# CYAN_EVSE_Power_board_v1_0.net
KiCad netlist of a schematic drawn in Altium Designer
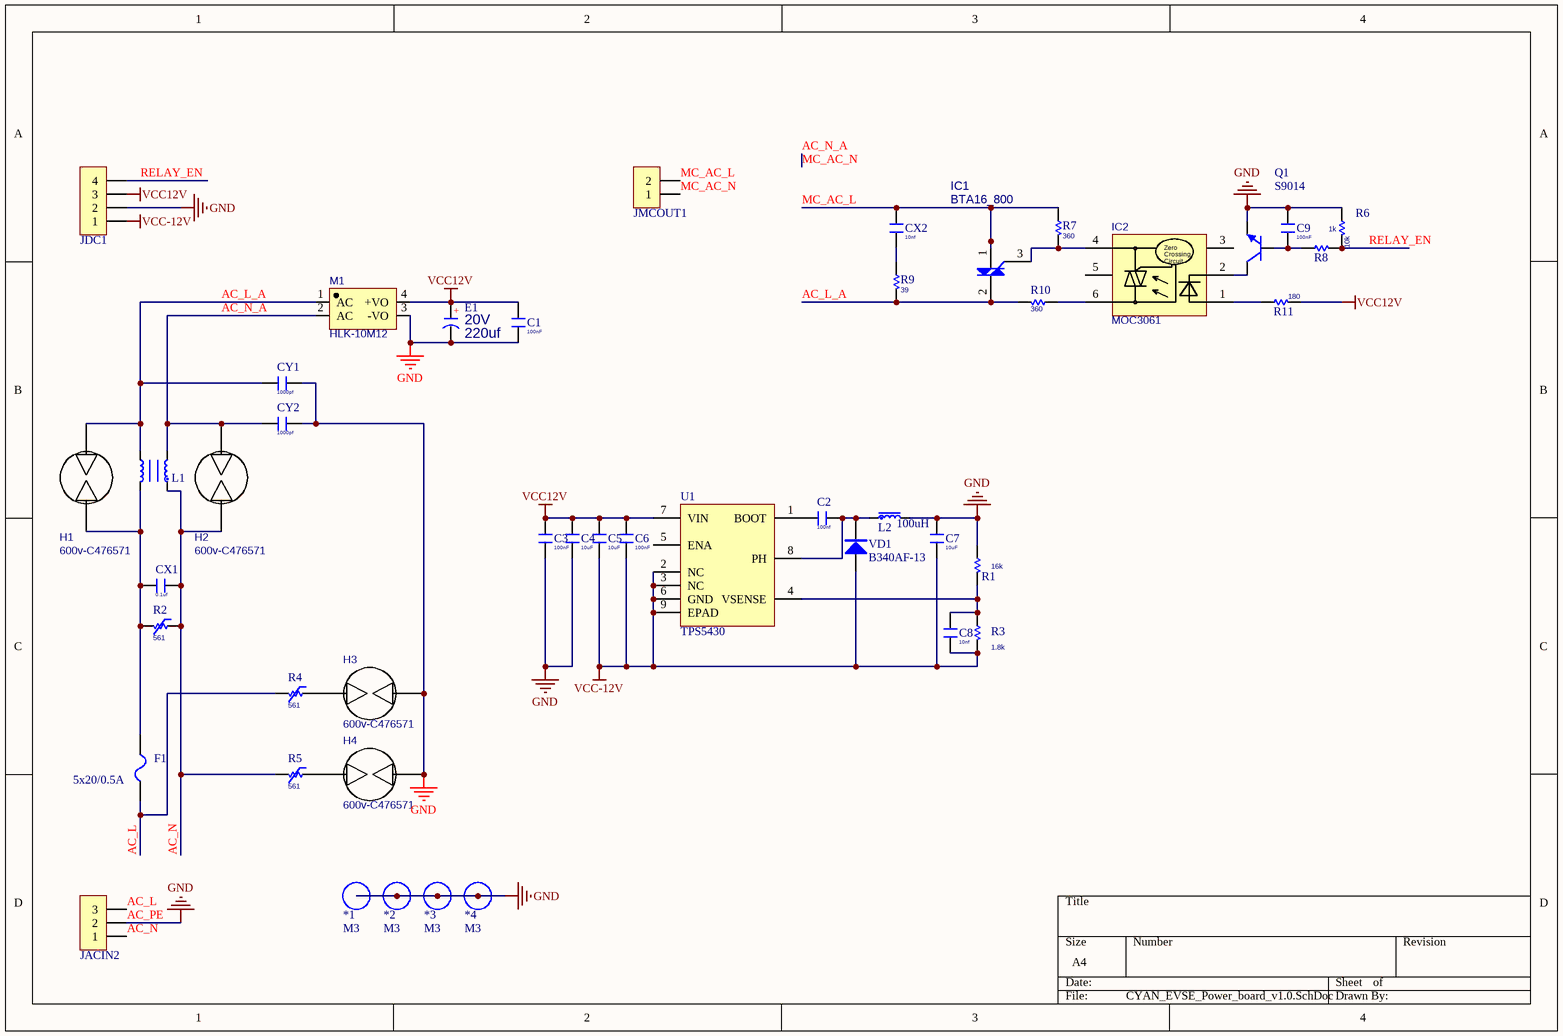
[diagram p0: CYAN_EVSE_Power_board_v1.0.SchDoc]

(export (version "E")
  (design (tool "Eeschema 10.0.6"))
  (components
    (comp (ref "*1")
      (value "M3")
      (footprint "M3 125X300")
      (description "铜柱孔")
      (libsource (lib "未分类器件") (part "M3"))
    )
    (comp (ref "*2")
      (value "M3")
      (footprint "M3 125X300")
      (description "铜柱孔")
      (libsource (lib "未分类器件") (part "M3"))
    )
    (comp (ref "*3")
      (value "M3")
      (footprint "M3 125X300")
      (description "铜柱孔")
      (libsource (lib "未分类器件") (part "M3"))
    )
    (comp (ref "*4")
      (value "M3")
      (footprint "M3 125X300")
      (description "铜柱孔")
      (libsource (lib "未分类器件") (part "M3"))
    )
    (comp (ref "C1")
      (value "100nF")
      (footprint "C 0805")
      (description "无极性贴片电容")
      (fields (field (name "VOLTAGE") "25V") (field (name "Comment") "C"))
      (libsource (lib "电阻-电容-电感") (part "C"))
    )
    (comp (ref "C2")
      (value "100nf")
      (footprint "C 0805")
      (description "无极性贴片电容")
      (fields (field (name "VOLTAGE") "50V") (field (name "Comment") "C"))
      (libsource (lib "电阻-电容-电感") (part "C"))
    )
    (comp (ref "C3")
      (value "100nF")
      (footprint "C 0805")
      (description "无极性贴片电容")
      (fields (field (name "VOLTAGE") "50V") (field (name "Comment") "C"))
      (libsource (lib "电阻-电容-电感") (part "C"))
    )
    (comp (ref "C4")
      (value "10uF")
      (footprint "C 0805")
      (description "无极性贴片电容")
      (fields (field (name "VOLTAGE") "50V") (field (name "Comment") "C"))
      (libsource (lib "电阻-电容-电感") (part "C"))
    )
    (comp (ref "C5")
      (value "10uF")
      (footprint "C 0805")
      (description "无极性贴片电容")
      (fields (field (name "VOLTAGE") "50V") (field (name "Comment") "C"))
      (libsource (lib "电阻-电容-电感") (part "C"))
    )
    (comp (ref "C6")
      (value "100nF")
      (footprint "C 0805")
      (description "无极性贴片电容")
      (fields (field (name "VOLTAGE") "50V") (field (name "Comment") "C"))
      (libsource (lib "电阻-电容-电感") (part "C"))
    )
    (comp (ref "C7")
      (value "10uF")
      (footprint "C 0805")
      (description "无极性贴片电容")
      (fields (field (name "VOLTAGE") "25V") (field (name "Comment") "C"))
      (libsource (lib "电阻-电容-电感") (part "C"))
    )
    (comp (ref "C8")
      (value "10nf")
      (footprint "C 0805")
      (description "无极性贴片电容")
      (fields (field (name "VOLTAGE") "50V") (field (name "Comment") "C"))
      (libsource (lib "电阻-电容-电感") (part "C"))
    )
    (comp (ref "C9")
      (value "100nF")
      (footprint "C 0805")
      (description "无极性贴片电容")
      (fields (field (name "VOLTAGE") "20V") (field (name "Comment") "C"))
      (libsource (lib "电阻-电容-电感") (part "C"))
    )
    (comp (ref "CX1")
      (value "0.1uf")
      (footprint "CX 10*13*11")
      (description "X电容")
      (fields (field (name "VOLTAGE") "10v") (field (name "Comment") "MKP-0.1uF275V"))
      (libsource (lib "电阻-电容-电感") (part "C-CX"))
    )
    (comp (ref "CX2")
      (value "10nf")
      (footprint "CX 10*13*11")
      (description "X电容")
      (fields (field (name "VOLTAGE") "440V") (field (name "Comment") "X1 安规电容"))
      (libsource (lib "电阻-电容-电感") (part "C-CX"))
    )
    (comp (ref "CY1")
      (value "1000pf")
      (footprint "CY 7.5*8*4")
      (description "高压陶瓷电容，Y电容")
      (fields (field (name "VOLTAGE") "250v") (field (name "Comment") "DCF102M26Y5VQ6B"))
      (libsource (lib "电阻-电容-电感") (part "C-CY"))
    )
    (comp (ref "CY2")
      (value "1000pf")
      (footprint "CY 7.5*8*4")
      (description "高压陶瓷电容，Y电容")
      (fields (field (name "VOLTAGE") "250v") (field (name "Comment") "DCF102M26Y5VQ6B"))
      (libsource (lib "电阻-电容-电感") (part "C-CY"))
    )
    (comp (ref "E1")
      (value "220uf")
      (footprint "CM D(6.3*5.4)")
      (description "贴片电解电容")
      (fields (field (name "VOLTAGE") "20V") (field (name "Comment") "C-CM"))
      (libsource (lib "电阻-电容-电感") (part "C-CM"))
    )
    (comp (ref "F1")
      (value "5x20/0.5A")
      (footprint "FU BLX-A")
      (description "5*20保险丝")
      (libsource (lib "保险丝-晶振") (part "FU 5x20"))
    )
    (comp (ref "H1")
      (value "600v-C476571")
      (footprint "GDT_SMD_L4.5-W3.2")
      (description "气体放电管")
      (libsource (lib "保险丝-晶振") (part "GDT"))
    )
    (comp (ref "H2")
      (value "600v-C476571")
      (footprint "GDT_SMD_L4.5-W3.2")
      (description "气体放电管")
      (libsource (lib "保险丝-晶振") (part "GDT"))
    )
    (comp (ref "H3")
      (value "600v-C476571")
      (footprint "GDT_SMD_L4.5-W3.2")
      (description "气体放电管")
      (libsource (lib "保险丝-晶振") (part "GDT"))
    )
    (comp (ref "H4")
      (value "600v-C476571")
      (footprint "GDT_SMD_L4.5-W3.2")
      (description "气体放电管")
      (libsource (lib "保险丝-晶振") (part "GDT"))
    )
    (comp (ref "IC1")
      (value "BTA16_800")
      (footprint "to:TO220A")
      (description "双向可控硅")
      (libsource (lib "场效应管-可控硅") (part "BTA12_600"))
    )
    (comp (ref "IC2")
      (value "MOC3061")
      (footprint "DIP6-300")
      (description "4(6)00v 带过0检测 光电可控硅 led电流15ma 1.3v")
      (fields (field (name "BOM_MANUFACTURER PART") "MOC3041M") (field (name "BOM_SUPPLIER PART") "C8921"))
      (libsource (lib "IC芯片") (part "MOC304(6)1"))
    )
    (comp (ref "JACIN2")
      (value "HDR-1X3")
      (footprint "KF2EDGK5.0-3P_H")
      (description "3P接插件")
      (libsource (lib "接插件") (part "Header 3"))
    )
    (comp (ref "JDC1")
      (value "HDR-1X4")
      (footprint "MC 1,5/ 4-G-3,81")
      (description "4P接插件")
      (libsource (lib "接插件") (part "Header 4"))
    )
    (comp (ref "JMCOUT1")
      (value "HDR-1X2")
      (footprint "MC 1,5/ 2-G-3,81")
      (description "2P接插件")
      (libsource (lib "接插件") (part "Header 2"))
    )
    (comp (ref "L1")
      (value "15mH")
      (footprint "UU9.8")
      (description "共模电感")
      (libsource (lib "电阻-电容-电感") (part "L-CMC"))
    )
    (comp (ref "L2")
      (value "100uH")
      (footprint "CD75")
      (description "贴片功率电感")
      (libsource (lib "电阻-电容-电感") (part "L-CD"))
    )
    (comp (ref "M1")
      (value "HLK-10M12")
      (footprint "PWRM-TH_HLK-10MXX")
      (description "HILINK 10W AC-DC 模块")
      (libsource (lib "模块") (part "HLK-10MXX"))
    )
    (comp (ref "Q1")
      (value "S9014")
      (footprint "SOT23-3N")
      (description "低噪放大-NPN型")
      (libsource (lib "三极管") (part "9014-SMD"))
    )
    (comp (ref "R1")
      (value "16k")
      (footprint "R 0805")
      (description "贴片电阻")
      (fields (field (name "Comment") "R"))
      (libsource (lib "电阻-电容-电感") (part "R"))
    )
    (comp (ref "R2")
      (value "561")
      (footprint "VDR 10D-7.5")
      (description "压敏电阻")
      (fields (field (name "Comment") "10d561k"))
      (libsource (lib "电阻-电容-电感") (part "R_VDR"))
    )
    (comp (ref "R3")
      (value "1.8k")
      (footprint "R 0805")
      (description "贴片电阻")
      (fields (field (name "Comment") "R"))
      (libsource (lib "电阻-电容-电感") (part "R"))
    )
    (comp (ref "R4")
      (value "561")
      (footprint "VDR 10D-7.5")
      (description "压敏电阻")
      (fields (field (name "Comment") "10d561k"))
      (libsource (lib "电阻-电容-电感") (part "R_VDR"))
    )
    (comp (ref "R5")
      (value "561")
      (footprint "VDR 10D-7.5")
      (description "压敏电阻")
      (fields (field (name "Comment") "10d561k"))
      (libsource (lib "电阻-电容-电感") (part "R_VDR"))
    )
    (comp (ref "R6")
      (value "10k")
      (footprint "R 0805")
      (description "贴片电阻")
      (fields (field (name "Comment") "R"))
      (libsource (lib "电阻-电容-电感") (part "R"))
    )
    (comp (ref "R7")
      (value "360")
      (footprint "RS 1/2W")
      (description "直插色环电阻")
      (fields (field (name "Comment") "R-CRR"))
      (libsource (lib "电阻-电容-电感") (part "R-CRR"))
    )
    (comp (ref "R8")
      (value "1k")
      (footprint "R 0805")
      (description "贴片电阻")
      (fields (field (name "Comment") "R"))
      (libsource (lib "电阻-电容-电感") (part "R"))
    )
    (comp (ref "R9")
      (value "39")
      (footprint "RS 2W")
      (description "直插色环电阻")
      (fields (field (name "Comment") "R-CRR"))
      (libsource (lib "电阻-电容-电感") (part "R-CRR"))
    )
    (comp (ref "R10")
      (value "360")
      (footprint "RS 1/2W")
      (description "直插色环电阻")
      (fields (field (name "Comment") "R-CRR"))
      (libsource (lib "电阻-电容-电感") (part "R-CRR"))
    )
    (comp (ref "R11")
      (value "180")
      (footprint "R 0805")
      (description "贴片电阻")
      (fields (field (name "Comment") "R"))
      (libsource (lib "电阻-电容-电感") (part "R"))
    )
    (comp (ref "U1")
      (value "TPS5430")
      (footprint "SOP8_EPAD_VIA")
      (description "3A 36v buck控制器，内置fet")
      (libsource (lib "IC芯片") (part "TPS5430"))
    )
    (comp (ref "VD1")
      (value "B340AF-13")
      (footprint "SMA")
      (description "肖特基二极管")
      (libsource (lib "二极管-整流桥") (part "SS14"))
    )
  )
  (nets
    (net (code "1") (name "/AC_L") (class "Default")
      (node (ref "F1") (pin "2") (pinfunction "2_2") (pintype "passive"))
      (node (ref "JACIN2") (pin "3") (pinfunction "3_3") (pintype "passive"))
      (node (ref "R4") (pin "2") (pinfunction "2_2") (pintype "passive"))
    )
    (net (code "2") (name "/AC_L_A") (class "Default")
      (node (ref "CY1") (pin "2") (pinfunction "2_2") (pintype "passive"))
      (node (ref "H1") (pin "2") (pinfunction "2_2") (pintype "passive"))
      (node (ref "IC1") (pin "2") (pinfunction "A2_2") (pintype "passive"))
      (node (ref "L1") (pin "3") (pinfunction "3_3") (pintype "passive"))
      (node (ref "M1") (pin "1") (pinfunction "AC_1") (pintype "passive"))
      (node (ref "R10") (pin "2") (pinfunction "2_2") (pintype "passive"))
      (node (ref "R9") (pin "2") (pinfunction "2_2") (pintype "passive"))
    )
    (net (code "3") (name "/AC_N") (class "Default")
      (node (ref "CX1") (pin "1") (pinfunction "1_1") (pintype "passive"))
      (node (ref "H2") (pin "1") (pinfunction "1_1") (pintype "passive"))
      (node (ref "JACIN2") (pin "1") (pinfunction "1_1") (pintype "passive"))
      (node (ref "L1") (pin "1") (pinfunction "1_1") (pintype "passive"))
      (node (ref "R2") (pin "1") (pinfunction "1_1") (pintype "passive"))
      (node (ref "R5") (pin "2") (pinfunction "2_2") (pintype "passive"))
    )
    (net (code "4") (name "/AC_N_A") (class "Default")
      (node (ref "CY2") (pin "2") (pinfunction "2_2") (pintype "passive"))
      (node (ref "H2") (pin "2") (pinfunction "2_2") (pintype "passive"))
      (node (ref "JMCOUT1") (pin "1") (pinfunction "1_1") (pintype "passive"))
      (node (ref "L1") (pin "2") (pinfunction "2_2") (pintype "passive"))
      (node (ref "M1") (pin "2") (pinfunction "AC_2") (pintype "passive"))
    )
    (net (code "5") (name "/MC_AC_L") (class "Default")
      (node (ref "CX2") (pin "1") (pinfunction "1_1") (pintype "passive"))
      (node (ref "IC1") (pin "1") (pinfunction "A1_1") (pintype "passive"))
      (node (ref "JMCOUT1") (pin "2") (pinfunction "2_2") (pintype "passive"))
      (node (ref "R7") (pin "1") (pinfunction "1_1") (pintype "passive"))
    )
    (net (code "6") (name "/RELAY_EN") (class "Default")
      (node (ref "JDC1") (pin "4") (pinfunction "4_4") (pintype "passive"))
      (node (ref "R6") (pin "2") (pinfunction "2_2") (pintype "passive"))
      (node (ref "R8") (pin "2") (pinfunction "2_2") (pintype "passive"))
    )
    (net (code "7") (name "GND") (class "Default")
      (node (ref "*1") (pin "0") (pinfunction "0_0") (pintype "passive"))
      (node (ref "*2") (pin "0") (pinfunction "0_0") (pintype "passive"))
      (node (ref "*3") (pin "0") (pinfunction "0_0") (pintype "passive"))
      (node (ref "*4") (pin "0") (pinfunction "0_0") (pintype "passive"))
      (node (ref "C1") (pin "1") (pinfunction "1_1") (pintype "passive"))
      (node (ref "C3") (pin "1") (pinfunction "1_1") (pintype "passive"))
      (node (ref "C4") (pin "2") (pinfunction "2_2") (pintype "passive"))
      (node (ref "C7") (pin "2") (pinfunction "2_2") (pintype "passive"))
      (node (ref "C9") (pin "1") (pinfunction "1_1") (pintype "passive"))
      (node (ref "CY1") (pin "1") (pinfunction "1_1") (pintype "passive"))
      (node (ref "CY2") (pin "1") (pinfunction "1_1") (pintype "passive"))
      (node (ref "E1") (pin "2") (pinfunction "2_2") (pintype "passive"))
      (node (ref "H3") (pin "2") (pinfunction "2_2") (pintype "passive"))
      (node (ref "H4") (pin "2") (pinfunction "2_2") (pintype "passive"))
      (node (ref "JACIN2") (pin "2") (pinfunction "2_2") (pintype "passive"))
      (node (ref "JDC1") (pin "2") (pinfunction "2_2") (pintype "passive"))
      (node (ref "L2") (pin "2") (pinfunction "2_2") (pintype "passive"))
      (node (ref "M1") (pin "3") (pinfunction "-VO_3") (pintype "passive"))
      (node (ref "Q1") (pin "2") (pinfunction "E_2") (pintype "passive"))
      (node (ref "R1") (pin "1") (pinfunction "1_1") (pintype "passive"))
      (node (ref "R6") (pin "1") (pinfunction "1_1") (pintype "passive"))
    )
    (net (code "8") (name "Net-(CX1-Pad2)") (class "Default")
      (node (ref "CX1") (pin "2") (pinfunction "2_2") (pintype "passive"))
      (node (ref "F1") (pin "1") (pinfunction "1_1") (pintype "passive"))
      (node (ref "H1") (pin "1") (pinfunction "1_1") (pintype "passive"))
      (node (ref "L1") (pin "4") (pinfunction "4_4") (pintype "passive"))
      (node (ref "R2") (pin "2") (pinfunction "2_2") (pintype "passive"))
    )
    (net (code "9") (name "Net-(CX2-Pad2)") (class "Default")
      (node (ref "CX2") (pin "2") (pinfunction "2_2") (pintype "passive"))
      (node (ref "R9") (pin "1") (pinfunction "1_1") (pintype "passive"))
    )
    (net (code "10") (name "Net-(H3-Pad1)") (class "Default")
      (node (ref "H3") (pin "1") (pinfunction "1_1") (pintype "passive"))
      (node (ref "R4") (pin "1") (pinfunction "1_1") (pintype "passive"))
    )
    (net (code "11") (name "Net-(H4-Pad1)") (class "Default")
      (node (ref "H4") (pin "1") (pinfunction "1_1") (pintype "passive"))
      (node (ref "R5") (pin "1") (pinfunction "1_1") (pintype "passive"))
    )
    (net (code "12") (name "Net-(IC1-G)") (class "Default")
      (node (ref "IC1") (pin "3") (pinfunction "G_3") (pintype "passive"))
      (node (ref "IC2") (pin "4") (pinfunction "T2_4") (pintype "passive"))
      (node (ref "R7") (pin "2") (pinfunction "2_2") (pintype "passive"))
    )
    (net (code "13") (name "Net-(IC2-A)") (class "Default")
      (node (ref "IC2") (pin "1") (pinfunction "A_1") (pintype "passive"))
      (node (ref "R11") (pin "1") (pinfunction "1_1") (pintype "passive"))
    )
    (net (code "14") (name "Net-(IC2-K)") (class "Default")
      (node (ref "IC2") (pin "2") (pinfunction "K_2") (pintype "passive"))
      (node (ref "Q1") (pin "3") (pinfunction "C_3") (pintype "passive"))
    )
    (net (code "15") (name "Net-(IC2-T1)") (class "Default")
      (node (ref "IC2") (pin "6") (pinfunction "T1_6") (pintype "passive"))
      (node (ref "R10") (pin "1") (pinfunction "1_1") (pintype "passive"))
    )
    (net (code "16") (name "Net-(Q1-B)") (class "Default")
      (node (ref "C9") (pin "2") (pinfunction "2_2") (pintype "passive"))
      (node (ref "Q1") (pin "1") (pinfunction "B_1") (pintype "passive"))
      (node (ref "R8") (pin "1") (pinfunction "1_1") (pintype "passive"))
    )
    (net (code "17") (name "Net-(U1-BOOT)") (class "Default")
      (node (ref "C2") (pin "1") (pinfunction "1_1") (pintype "passive"))
      (node (ref "U1") (pin "1") (pinfunction "BOOT_1") (pintype "passive"))
    )
    (net (code "18") (name "Net-(U1-PH)") (class "Default")
      (node (ref "C2") (pin "2") (pinfunction "2_2") (pintype "passive"))
      (node (ref "L2") (pin "1") (pinfunction "1_1") (pintype "passive"))
      (node (ref "U1") (pin "8") (pinfunction "PH_8") (pintype "passive"))
      (node (ref "VD1") (pin "2") (pinfunction "K_2") (pintype "passive"))
    )
    (net (code "19") (name "Net-(U1-VSENSE)") (class "Default")
      (node (ref "C8") (pin "1") (pinfunction "1_1") (pintype "passive"))
      (node (ref "R1") (pin "2") (pinfunction "2_2") (pintype "passive"))
      (node (ref "R3") (pin "1") (pinfunction "1_1") (pintype "passive"))
      (node (ref "U1") (pin "4") (pinfunction "VSENSE_4") (pintype "passive"))
    )
    (net (code "20") (name "VCC-12V") (class "Default")
      (node (ref "C5") (pin "1") (pinfunction "1_1") (pintype "passive"))
      (node (ref "C6") (pin "1") (pinfunction "1_1") (pintype "passive"))
      (node (ref "C7") (pin "1") (pinfunction "1_1") (pintype "passive"))
      (node (ref "C8") (pin "2") (pinfunction "2_2") (pintype "passive"))
      (node (ref "JDC1") (pin "1") (pinfunction "1_1") (pintype "passive"))
      (node (ref "R3") (pin "2") (pinfunction "2_2") (pintype "passive"))
      (node (ref "U1") (pin "2") (pinfunction "NC_2") (pintype "passive"))
      (node (ref "U1") (pin "3") (pinfunction "NC_3") (pintype "passive"))
      (node (ref "U1") (pin "6") (pinfunction "GND_6") (pintype "passive"))
      (node (ref "U1") (pin "9") (pinfunction "EPAD_9") (pintype "passive"))
      (node (ref "VD1") (pin "1") (pinfunction "A_1") (pintype "passive"))
    )
    (net (code "21") (name "VCC12V") (class "Default")
      (node (ref "C1") (pin "2") (pinfunction "2_2") (pintype "passive"))
      (node (ref "C3") (pin "2") (pinfunction "2_2") (pintype "passive"))
      (node (ref "C4") (pin "1") (pinfunction "1_1") (pintype "passive"))
      (node (ref "C5") (pin "2") (pinfunction "2_2") (pintype "passive"))
      (node (ref "C6") (pin "2") (pinfunction "2_2") (pintype "passive"))
      (node (ref "E1") (pin "1") (pinfunction "1_1") (pintype "passive"))
      (node (ref "JDC1") (pin "3") (pinfunction "3_3") (pintype "passive"))
      (node (ref "M1") (pin "4") (pinfunction "+VO_4") (pintype "passive"))
      (node (ref "R11") (pin "2") (pinfunction "2_2") (pintype "passive"))
      (node (ref "U1") (pin "7") (pinfunction "VIN_7") (pintype "passive"))
    )
    (net (code "22") (name "unconnected-(IC2-NC-Pad3)") (class "Default")
      (node (ref "IC2") (pin "3") (pinfunction "NC_3") (pintype "passive"))
    )
    (net (code "23") (name "unconnected-(IC2-NC-Pad5)") (class "Default")
      (node (ref "IC2") (pin "5") (pinfunction "NC_5") (pintype "passive"))
    )
    (net (code "24") (name "unconnected-(U1-ENA-Pad5)") (class "Default")
      (node (ref "U1") (pin "5") (pinfunction "ENA_5") (pintype "passive"))
    )
  )
)
